# decoder.net
KiCad netlist of a schematic drawn in EAGLE
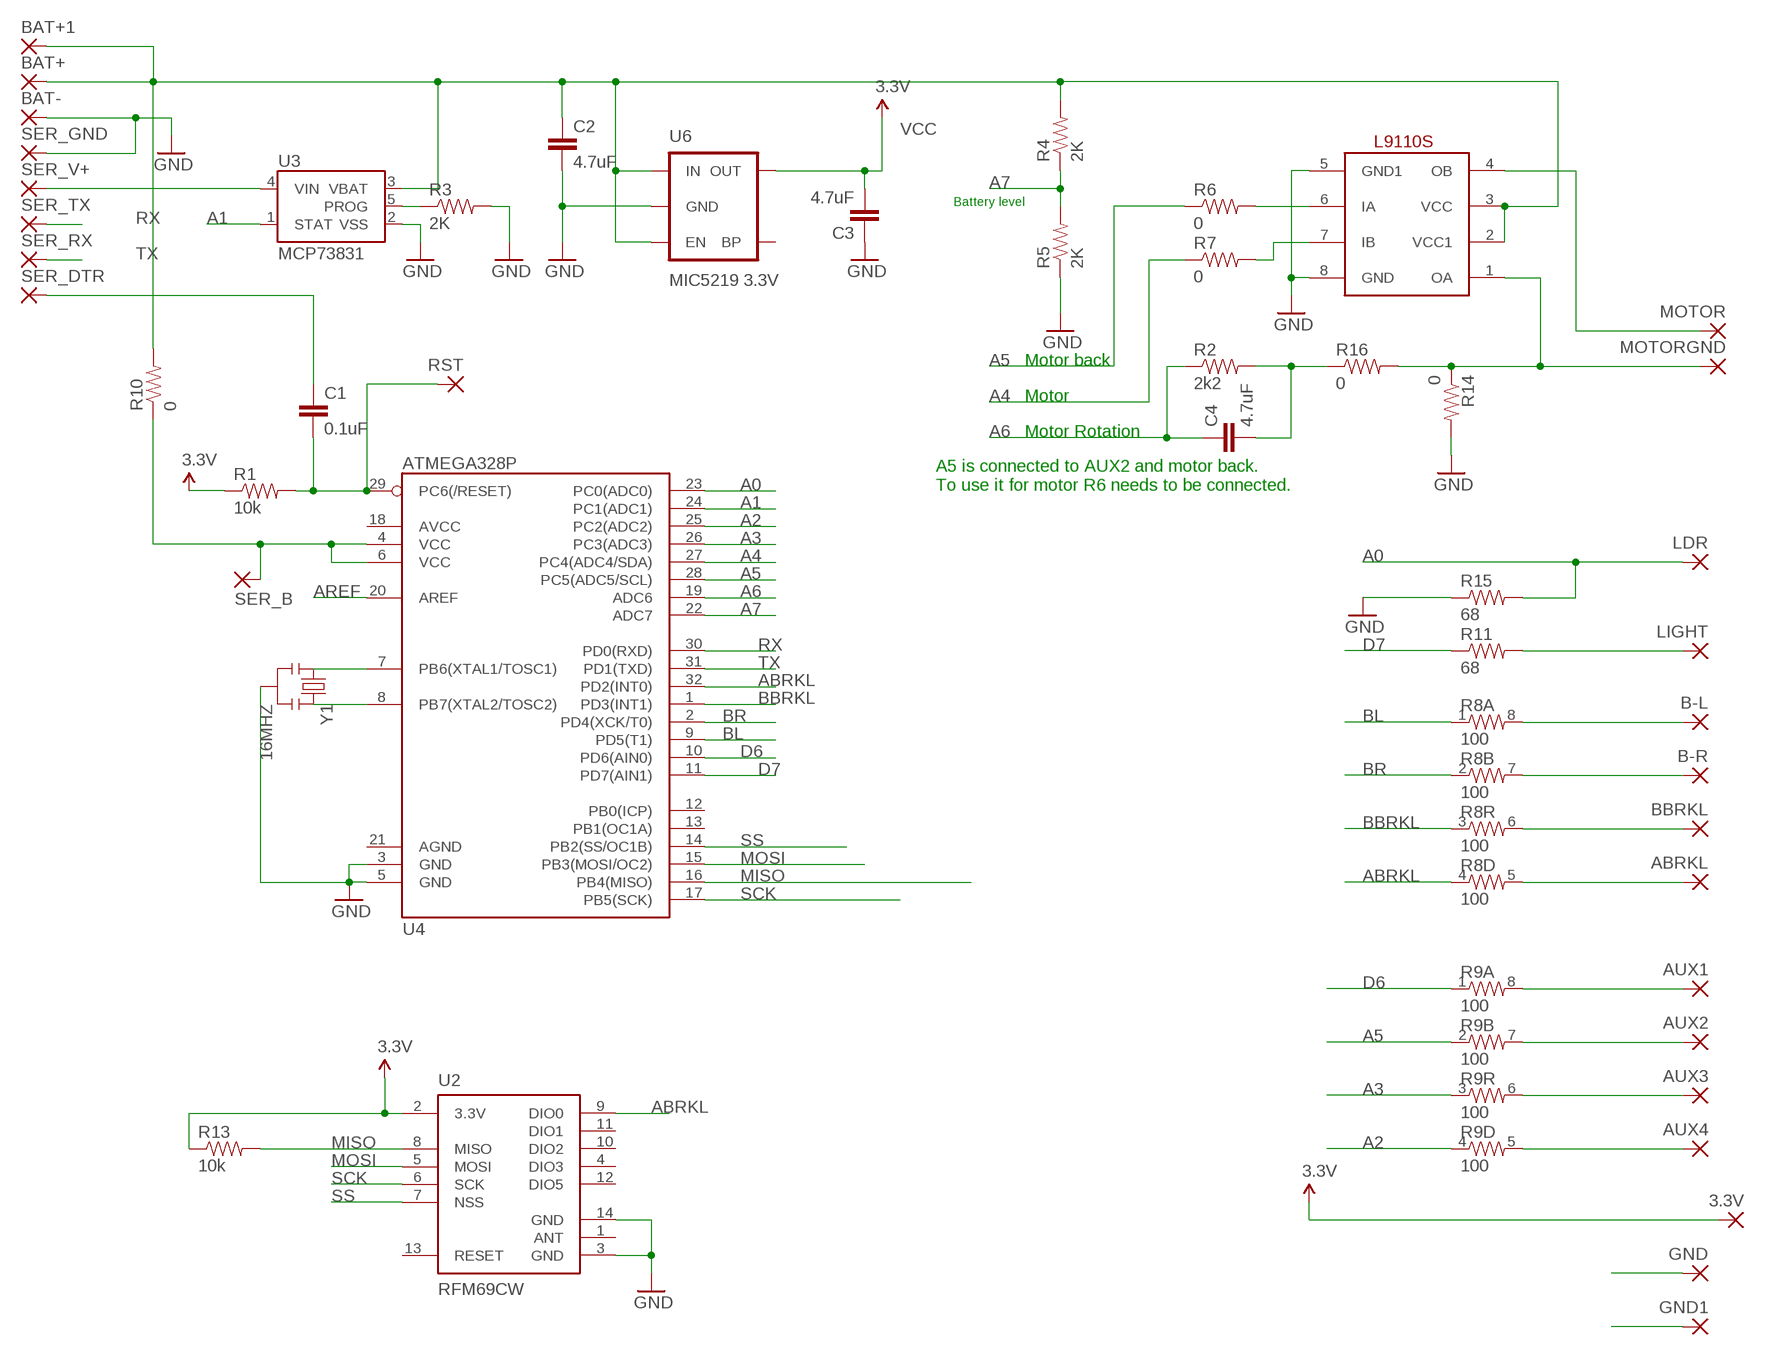
[diagram p0: schematic, sheet 1]

(export (version "E")
  (design (tool "Eeschema 10.0.6"))
  (components
    (comp (ref "3.3V")
      (value "SMD2")
      (footprint "eagle-import:SMD1,27-2,54")
      (libsource (lib "eagle-import") (part "SMD2"))
    )
    (comp (ref "ABRKL")
      (value "SMD2")
      (footprint "eagle-import:SMD1,27-2,54")
      (libsource (lib "eagle-import") (part "SMD2"))
    )
    (comp (ref "AUX1")
      (value "SMD2")
      (footprint "eagle-import:SMD1,27-2,54")
      (libsource (lib "eagle-import") (part "SMD2"))
    )
    (comp (ref "AUX2")
      (value "SMD2")
      (footprint "eagle-import:SMD1,27-2,54")
      (libsource (lib "eagle-import") (part "SMD2"))
    )
    (comp (ref "AUX3")
      (value "SMD2")
      (footprint "eagle-import:SMD1,27-2,54")
      (libsource (lib "eagle-import") (part "SMD2"))
    )
    (comp (ref "AUX4")
      (value "SMD2")
      (footprint "eagle-import:SMD1,27-2,54")
      (libsource (lib "eagle-import") (part "SMD2"))
    )
    (comp (ref "B-L")
      (value "SMD2")
      (footprint "eagle-import:SMD1,27-2,54")
      (libsource (lib "eagle-import") (part "SMD2"))
    )
    (comp (ref "B-R")
      (value "SMD2")
      (footprint "eagle-import:SMD1,27-2,54")
      (libsource (lib "eagle-import") (part "SMD2"))
    )
    (comp (ref "BAT+")
      (value "SMD2")
      (footprint "eagle-import:SMD1,27-2,54")
      (libsource (lib "eagle-import") (part "SMD2"))
    )
    (comp (ref "BAT+1")
      (value "SMD2")
      (footprint "eagle-import:SMD1,27-2,54")
      (libsource (lib "eagle-import") (part "SMD2"))
    )
    (comp (ref "BAT-")
      (value "SMD2")
      (footprint "eagle-import:SMD1,27-2,54")
      (libsource (lib "eagle-import") (part "SMD2"))
    )
    (comp (ref "BBRKL")
      (value "SMD2")
      (footprint "eagle-import:SMD1,27-2,54")
      (libsource (lib "eagle-import") (part "SMD2"))
    )
    (comp (ref "C1")
      (value "0.1uF")
      (footprint "eagle-import:0805")
      (libsource (lib "eagle-import") (part "CAP0805"))
    )
    (comp (ref "C2")
      (value "4.7uF")
      (footprint "eagle-import:0805")
      (libsource (lib "eagle-import") (part "CAP0805"))
    )
    (comp (ref "C3")
      (value "4.7uF")
      (footprint "eagle-import:0805")
      (libsource (lib "eagle-import") (part "CAP0805"))
    )
    (comp (ref "C4")
      (value "4.7uF")
      (footprint "eagle-import:0805")
      (libsource (lib "eagle-import") (part "CAP0805"))
    )
    (comp (ref "GND")
      (value "SMD2")
      (footprint "eagle-import:SMD1,27-2,54")
      (libsource (lib "eagle-import") (part "SMD2"))
    )
    (comp (ref "GND1")
      (value "SMD2")
      (footprint "eagle-import:SMD1,27-2,54")
      (libsource (lib "eagle-import") (part "SMD2"))
    )
    (comp (ref "LDR")
      (value "SMD2")
      (footprint "eagle-import:SMD1,27-2,54")
      (libsource (lib "eagle-import") (part "SMD2"))
    )
    (comp (ref "LIGHT")
      (value "SMD2")
      (footprint "eagle-import:SMD1,27-2,54")
      (libsource (lib "eagle-import") (part "SMD2"))
    )
    (comp (ref "MDRIVER")
      (value "L9110S")
      (footprint "eagle-import:SO08")
      (libsource (lib "eagle-import") (part "L9110S"))
    )
    (comp (ref "MOTOR")
      (value "SMD2")
      (footprint "eagle-import:SMD1,27-2,54")
      (libsource (lib "eagle-import") (part "SMD2"))
    )
    (comp (ref "MOTORGND")
      (value "SMD2")
      (footprint "eagle-import:SMD1,27-2,54")
      (libsource (lib "eagle-import") (part "SMD2"))
    )
    (comp (ref "R1")
      (value "10k")
      (footprint "eagle-import:0603-RES")
      (libsource (lib "eagle-import") (part "RESISTOR0603-RES"))
    )
    (comp (ref "R2")
      (value "2k2")
      (footprint "eagle-import:0603-RES")
      (libsource (lib "eagle-import") (part "RESISTOR0603-RES"))
    )
    (comp (ref "R3")
      (value "2K")
      (footprint "eagle-import:0603-RES")
      (libsource (lib "eagle-import") (part "RESISTOR0603-RES"))
    )
    (comp (ref "R4")
      (value "2K")
      (footprint "eagle-import:0603-RES")
      (libsource (lib "eagle-import") (part "RESISTOR0603-RES"))
    )
    (comp (ref "R5")
      (value "2K")
      (footprint "eagle-import:0603-RES")
      (libsource (lib "eagle-import") (part "RESISTOR0603-RES"))
    )
    (comp (ref "R6")
      (value "0")
      (footprint "eagle-import:0603-RES")
      (libsource (lib "eagle-import") (part "RESISTOR0603-RES"))
    )
    (comp (ref "R7")
      (value "0")
      (footprint "eagle-import:0603-RES")
      (libsource (lib "eagle-import") (part "RESISTOR0603-RES"))
    )
    (comp (ref "R8")
      (value "100")
      (footprint "eagle-import:0603-ARV")
      (libsource (lib "eagle-import") (part "RESISTOR-ARRAY0603-ARV"))
    )
    (comp (ref "R9")
      (value "100")
      (footprint "eagle-import:0603-ARV")
      (libsource (lib "eagle-import") (part "RESISTOR-ARRAY0603-ARV"))
    )
    (comp (ref "R10")
      (value "0")
      (footprint "eagle-import:0603-RES")
      (libsource (lib "eagle-import") (part "RESISTOR0603-RES"))
    )
    (comp (ref "R11")
      (value "68")
      (footprint "eagle-import:0603-RES")
      (libsource (lib "eagle-import") (part "RESISTOR0603-RES"))
    )
    (comp (ref "R13")
      (value "10k")
      (footprint "eagle-import:0603-RES")
      (libsource (lib "eagle-import") (part "RESISTOR0603-RES"))
    )
    (comp (ref "R14")
      (value "0")
      (footprint "eagle-import:0603-RES")
      (libsource (lib "eagle-import") (part "RESISTOR0603-RES"))
    )
    (comp (ref "R15")
      (value "68")
      (footprint "eagle-import:0603-RES")
      (libsource (lib "eagle-import") (part "RESISTOR0603-RES"))
    )
    (comp (ref "R16")
      (value "0")
      (footprint "eagle-import:0603-RES")
      (libsource (lib "eagle-import") (part "RESISTOR0603-RES"))
    )
    (comp (ref "RST")
      (value "SMD2")
      (footprint "eagle-import:SMD1,27-2,54")
      (libsource (lib "eagle-import") (part "SMD2"))
    )
    (comp (ref "SER_B")
      (value "SMD2")
      (footprint "eagle-import:SMD1,27-2,54")
      (libsource (lib "eagle-import") (part "SMD2"))
    )
    (comp (ref "SER_DTR")
      (value "SMD2")
      (footprint "eagle-import:SMD1,27-2,54")
      (libsource (lib "eagle-import") (part "SMD2"))
    )
    (comp (ref "SER_GND")
      (value "SMD2")
      (footprint "eagle-import:SMD1,27-2,54")
      (libsource (lib "eagle-import") (part "SMD2"))
    )
    (comp (ref "SER_RX")
      (value "SMD2")
      (footprint "eagle-import:SMD1,27-2,54")
      (libsource (lib "eagle-import") (part "SMD2"))
    )
    (comp (ref "SER_TX")
      (value "SMD2")
      (footprint "eagle-import:SMD1,27-2,54")
      (libsource (lib "eagle-import") (part "SMD2"))
    )
    (comp (ref "SER_V+")
      (value "SMD2")
      (footprint "eagle-import:SMD1,27-2,54")
      (libsource (lib "eagle-import") (part "SMD2"))
    )
    (comp (ref "U2")
      (value "RFM69CW")
      (footprint "eagle-import:RFM69CW-XXXS2")
      (libsource (lib "eagle-import") (part "RFM69CW"))
    )
    (comp (ref "U3")
      (value "MCP73831")
      (footprint "eagle-import:SOT23-5")
      (libsource (lib "eagle-import") (part "MCP73831"))
    )
    (comp (ref "U4")
      (value "ATMEGA328P")
      (footprint "eagle-import:TQFP32-08")
      (libsource (lib "eagle-import") (part "ATMEGA328_SMT"))
    )
    (comp (ref "U6")
      (value "MIC5219 3.3V")
      (footprint "eagle-import:SOT23-5")
      (libsource (lib "eagle-import") (part "V_REG_MIC52193.3V"))
    )
    (comp (ref "Y1")
      (value "16MHZ")
      (footprint "eagle-import:RESONATOR-SMD")
      (libsource (lib "eagle-import") (part "RESONATOR16MHZ"))
    )
  )
  (nets
    (net (code "1") (name "/A0") (class "Default")
      (node (ref "LDR") (pin "1") (pinfunction "P_1") (pintype "passive"))
      (node (ref "R15") (pin "2") (pinfunction "2_2") (pintype "passive"))
      (node (ref "U4") (pin "23") (pinfunction "PC0(ADC0)_23") (pintype "bidirectional"))
    )
    (net (code "2") (name "/A1") (class "Default")
      (node (ref "U3") (pin "1") (pinfunction "STAT_1") (pintype "output"))
      (node (ref "U4") (pin "24") (pinfunction "PC1(ADC1)_24") (pintype "bidirectional"))
    )
    (net (code "3") (name "/A2") (class "Default")
      (node (ref "R9") (pin "4") (pinfunction "1_4") (pintype "passive"))
      (node (ref "U4") (pin "25") (pinfunction "PC2(ADC2)_25") (pintype "bidirectional"))
    )
    (net (code "4") (name "/A3") (class "Default")
      (node (ref "R9") (pin "3") (pinfunction "1_3") (pintype "passive"))
      (node (ref "U4") (pin "26") (pinfunction "PC3(ADC3)_26") (pintype "bidirectional"))
    )
    (net (code "5") (name "/A4") (class "Default")
      (node (ref "R7") (pin "1") (pinfunction "1_1") (pintype "passive"))
      (node (ref "U4") (pin "27") (pinfunction "PC4(ADC4/SDA)_27") (pintype "bidirectional"))
    )
    (net (code "6") (name "/A5") (class "Default")
      (node (ref "R6") (pin "1") (pinfunction "1_1") (pintype "passive"))
      (node (ref "R9") (pin "2") (pinfunction "1_2") (pintype "passive"))
      (node (ref "U4") (pin "28") (pinfunction "PC5(ADC5/SCL)_28") (pintype "bidirectional"))
    )
    (net (code "7") (name "/A6") (class "Default")
      (node (ref "C4") (pin "1") (pinfunction "1_1") (pintype "passive"))
      (node (ref "R2") (pin "1") (pinfunction "1_1") (pintype "passive"))
      (node (ref "U4") (pin "19") (pinfunction "ADC6_19") (pintype "bidirectional"))
    )
    (net (code "8") (name "/A7") (class "Default")
      (node (ref "R4") (pin "1") (pinfunction "1_1") (pintype "passive"))
      (node (ref "R5") (pin "2") (pinfunction "2_2") (pintype "passive"))
      (node (ref "U4") (pin "22") (pinfunction "ADC7_22") (pintype "bidirectional"))
    )
    (net (code "9") (name "/ABRKL") (class "Default")
      (node (ref "R8") (pin "4") (pinfunction "1_4") (pintype "passive"))
      (node (ref "U2") (pin "9") (pinfunction "DIO0_9") (pintype "bidirectional"))
      (node (ref "U4") (pin "32") (pinfunction "PD2(INT0)_32") (pintype "bidirectional"))
    )
    (net (code "10") (name "/AREF") (class "Default")
      (node (ref "U4") (pin "20") (pinfunction "AREF_20") (pintype "bidirectional"))
    )
    (net (code "11") (name "/BBRKL") (class "Default")
      (node (ref "R8") (pin "3") (pinfunction "1_3") (pintype "passive"))
      (node (ref "U4") (pin "1") (pinfunction "PD3(INT1)_1") (pintype "bidirectional"))
    )
    (net (code "12") (name "/BL") (class "Default")
      (node (ref "R8") (pin "1") (pinfunction "1_1") (pintype "passive"))
      (node (ref "U4") (pin "9") (pinfunction "PD5(T1)_9") (pintype "bidirectional"))
    )
    (net (code "13") (name "/BR") (class "Default")
      (node (ref "R8") (pin "2") (pinfunction "1_2") (pintype "passive"))
      (node (ref "U4") (pin "2") (pinfunction "PD4(XCK/T0)_2") (pintype "bidirectional"))
    )
    (net (code "14") (name "/D6") (class "Default")
      (node (ref "R9") (pin "1") (pinfunction "1_1") (pintype "passive"))
      (node (ref "U4") (pin "10") (pinfunction "PD6(AIN0)_10") (pintype "bidirectional"))
    )
    (net (code "15") (name "/D7") (class "Default")
      (node (ref "R11") (pin "1") (pinfunction "1_1") (pintype "passive"))
      (node (ref "U4") (pin "11") (pinfunction "PD7(AIN1)_11") (pintype "bidirectional"))
    )
    (net (code "16") (name "/MISO") (class "Default")
      (node (ref "R13") (pin "2") (pinfunction "2_2") (pintype "passive"))
      (node (ref "U2") (pin "8") (pinfunction "MISO_8") (pintype "bidirectional"))
      (node (ref "U4") (pin "16") (pinfunction "PB4(MISO)_16") (pintype "bidirectional"))
    )
    (net (code "17") (name "/MOSI") (class "Default")
      (node (ref "U2") (pin "5") (pinfunction "MOSI_5") (pintype "input"))
      (node (ref "U4") (pin "15") (pinfunction "PB3(MOSI/OC2)_15") (pintype "bidirectional"))
    )
    (net (code "18") (name "/RX") (class "Default")
      (node (ref "SER_TX") (pin "1") (pinfunction "P_1") (pintype "passive"))
      (node (ref "U4") (pin "30") (pinfunction "PD0(RXD)_30") (pintype "bidirectional"))
    )
    (net (code "19") (name "/SCK") (class "Default")
      (node (ref "U2") (pin "6") (pinfunction "SCK_6") (pintype "input"))
      (node (ref "U4") (pin "17") (pinfunction "PB5(SCK)_17") (pintype "bidirectional"))
    )
    (net (code "20") (name "/SS") (class "Default")
      (node (ref "U2") (pin "7") (pinfunction "NSS_7") (pintype "input"))
      (node (ref "U4") (pin "14") (pinfunction "PB2(SS/OC1B)_14") (pintype "bidirectional"))
    )
    (net (code "21") (name "/TX") (class "Default")
      (node (ref "SER_RX") (pin "1") (pinfunction "P_1") (pintype "passive"))
      (node (ref "U4") (pin "31") (pinfunction "PD1(TXD)_31") (pintype "bidirectional"))
    )
    (net (code "22") (name "3.3V") (class "Default")
      (node (ref "3.3V") (pin "1") (pinfunction "P_1") (pintype "passive"))
      (node (ref "C3") (pin "2") (pinfunction "2_2") (pintype "passive"))
      (node (ref "R1") (pin "1") (pinfunction "1_1") (pintype "passive"))
      (node (ref "R13") (pin "1") (pinfunction "1_1") (pintype "passive"))
      (node (ref "U2") (pin "2") (pinfunction "3.3V_2") (pintype "power_in"))
      (node (ref "U6") (pin "5") (pinfunction "OUT_5") (pintype "passive"))
    )
    (net (code "23") (name "GND") (class "Default")
      (node (ref "BAT-") (pin "1") (pinfunction "P_1") (pintype "passive"))
      (node (ref "C2") (pin "2") (pinfunction "2_2") (pintype "passive"))
      (node (ref "C3") (pin "1") (pinfunction "1_1") (pintype "passive"))
      (node (ref "GND") (pin "1") (pinfunction "P_1") (pintype "passive"))
      (node (ref "GND1") (pin "1") (pinfunction "P_1") (pintype "passive"))
      (node (ref "MDRIVER") (pin "5") (pinfunction "GND1_5") (pintype "passive"))
      (node (ref "MDRIVER") (pin "8") (pinfunction "GND_8") (pintype "output"))
      (node (ref "R14") (pin "2") (pinfunction "2_2") (pintype "passive"))
      (node (ref "R15") (pin "1") (pinfunction "1_1") (pintype "passive"))
      (node (ref "R3") (pin "2") (pinfunction "2_2") (pintype "passive"))
      (node (ref "R5") (pin "1") (pinfunction "1_1") (pintype "passive"))
      (node (ref "SER_GND") (pin "1") (pinfunction "P_1") (pintype "passive"))
      (node (ref "U2") (pin "14") (pinfunction "GND_14") (pintype "power_in"))
      (node (ref "U2") (pin "3") (pinfunction "GND_3") (pintype "power_in"))
      (node (ref "U3") (pin "2") (pinfunction "VSS_2") (pintype "power_in"))
      (node (ref "U4") (pin "3") (pinfunction "GND_3") (pintype "bidirectional"))
      (node (ref "U4") (pin "5") (pinfunction "GND_5") (pintype "bidirectional"))
      (node (ref "U6") (pin "2") (pinfunction "GND_2") (pintype "input"))
      (node (ref "Y1") (pin "2") (pinfunction "2_2") (pintype "passive"))
    )
    (net (code "24") (name "Net-(ABRKL-P)") (class "Default")
      (node (ref "ABRKL") (pin "1") (pinfunction "P_1") (pintype "passive"))
      (node (ref "R8") (pin "5") (pinfunction "2_5") (pintype "passive"))
    )
    (net (code "25") (name "Net-(AUX1-P)") (class "Default")
      (node (ref "AUX1") (pin "1") (pinfunction "P_1") (pintype "passive"))
      (node (ref "R9") (pin "8") (pinfunction "2_8") (pintype "passive"))
    )
    (net (code "26") (name "Net-(AUX2-P)") (class "Default")
      (node (ref "AUX2") (pin "1") (pinfunction "P_1") (pintype "passive"))
      (node (ref "R9") (pin "7") (pinfunction "2_7") (pintype "passive"))
    )
    (net (code "27") (name "Net-(AUX3-P)") (class "Default")
      (node (ref "AUX3") (pin "1") (pinfunction "P_1") (pintype "passive"))
      (node (ref "R9") (pin "6") (pinfunction "2_6") (pintype "passive"))
    )
    (net (code "28") (name "Net-(AUX4-P)") (class "Default")
      (node (ref "AUX4") (pin "1") (pinfunction "P_1") (pintype "passive"))
      (node (ref "R9") (pin "5") (pinfunction "2_5") (pintype "passive"))
    )
    (net (code "29") (name "Net-(B-L-P)") (class "Default")
      (node (ref "B-L") (pin "1") (pinfunction "P_1") (pintype "passive"))
      (node (ref "R8") (pin "8") (pinfunction "2_8") (pintype "passive"))
    )
    (net (code "30") (name "Net-(B-R-P)") (class "Default")
      (node (ref "B-R") (pin "1") (pinfunction "P_1") (pintype "passive"))
      (node (ref "R8") (pin "7") (pinfunction "2_7") (pintype "passive"))
    )
    (net (code "31") (name "Net-(BAT+-P)") (class "Default")
      (node (ref "BAT+") (pin "1") (pinfunction "P_1") (pintype "passive"))
      (node (ref "BAT+1") (pin "1") (pinfunction "P_1") (pintype "passive"))
      (node (ref "C2") (pin "1") (pinfunction "1_1") (pintype "passive"))
      (node (ref "MDRIVER") (pin "2") (pinfunction "VCC1_2") (pintype "input"))
      (node (ref "MDRIVER") (pin "3") (pinfunction "VCC_3") (pintype "input"))
      (node (ref "R10") (pin "2") (pinfunction "2_2") (pintype "passive"))
      (node (ref "R4") (pin "2") (pinfunction "2_2") (pintype "passive"))
      (node (ref "U3") (pin "3") (pinfunction "VBAT_3") (pintype "power_in"))
      (node (ref "U6") (pin "1") (pinfunction "IN_1") (pintype "input"))
      (node (ref "U6") (pin "3") (pinfunction "EN_3") (pintype "input"))
    )
    (net (code "32") (name "Net-(BBRKL-P)") (class "Default")
      (node (ref "BBRKL") (pin "1") (pinfunction "P_1") (pintype "passive"))
      (node (ref "R8") (pin "6") (pinfunction "2_6") (pintype "passive"))
    )
    (net (code "33") (name "Net-(C4-Pad2)") (class "Default")
      (node (ref "C4") (pin "2") (pinfunction "2_2") (pintype "passive"))
      (node (ref "R16") (pin "1") (pinfunction "1_1") (pintype "passive"))
      (node (ref "R2") (pin "2") (pinfunction "2_2") (pintype "passive"))
    )
    (net (code "34") (name "Net-(LIGHT-P)") (class "Default")
      (node (ref "LIGHT") (pin "1") (pinfunction "P_1") (pintype "passive"))
      (node (ref "R11") (pin "2") (pinfunction "2_2") (pintype "passive"))
    )
    (net (code "35") (name "Net-(MDRIVER-IA)") (class "Default")
      (node (ref "MDRIVER") (pin "6") (pinfunction "IA_6") (pintype "passive"))
      (node (ref "R6") (pin "2") (pinfunction "2_2") (pintype "passive"))
    )
    (net (code "36") (name "Net-(MDRIVER-IB)") (class "Default")
      (node (ref "MDRIVER") (pin "7") (pinfunction "IB_7") (pintype "output"))
      (node (ref "R7") (pin "2") (pinfunction "2_2") (pintype "passive"))
    )
    (net (code "37") (name "Net-(MDRIVER-OA)") (class "Default")
      (node (ref "MDRIVER") (pin "1") (pinfunction "OA_1") (pintype "power_in"))
      (node (ref "MOTORGND") (pin "1") (pinfunction "P_1") (pintype "passive"))
      (node (ref "R14") (pin "1") (pinfunction "1_1") (pintype "passive"))
      (node (ref "R16") (pin "2") (pinfunction "2_2") (pintype "passive"))
    )
    (net (code "38") (name "Net-(MDRIVER-OB)") (class "Default")
      (node (ref "MDRIVER") (pin "4") (pinfunction "OB_4") (pintype "power_in"))
      (node (ref "MOTOR") (pin "1") (pinfunction "P_1") (pintype "passive"))
    )
    (net (code "39") (name "Net-(RST-P)") (class "Default")
      (node (ref "C1") (pin "2") (pinfunction "2_2") (pintype "passive"))
      (node (ref "R1") (pin "2") (pinfunction "2_2") (pintype "passive"))
      (node (ref "RST") (pin "1") (pinfunction "P_1") (pintype "passive"))
      (node (ref "U4") (pin "29") (pinfunction "PC6(/RESET)_29") (pintype "bidirectional"))
    )
    (net (code "40") (name "Net-(SER_B-P)") (class "Default")
      (node (ref "R10") (pin "1") (pinfunction "1_1") (pintype "passive"))
      (node (ref "SER_B") (pin "1") (pinfunction "P_1") (pintype "passive"))
      (node (ref "U4") (pin "4") (pinfunction "VCC_4") (pintype "bidirectional"))
      (node (ref "U4") (pin "6") (pinfunction "VCC_6") (pintype "bidirectional"))
    )
    (net (code "41") (name "Net-(SER_DTR-P)") (class "Default")
      (node (ref "C1") (pin "1") (pinfunction "1_1") (pintype "passive"))
      (node (ref "SER_DTR") (pin "1") (pinfunction "P_1") (pintype "passive"))
    )
    (net (code "42") (name "Net-(SER_V+-P)") (class "Default")
      (node (ref "SER_V+") (pin "1") (pinfunction "P_1") (pintype "passive"))
      (node (ref "U3") (pin "4") (pinfunction "VIN_4") (pintype "power_in"))
    )
    (net (code "43") (name "Net-(U3-PROG)") (class "Default")
      (node (ref "R3") (pin "1") (pinfunction "1_1") (pintype "passive"))
      (node (ref "U3") (pin "5") (pinfunction "PROG_5") (pintype "input"))
    )
    (net (code "44") (name "Net-(U4-PB6(XTAL1{slash}TOSC1))") (class "Default")
      (node (ref "U4") (pin "7") (pinfunction "PB6(XTAL1/TOSC1)_7") (pintype "bidirectional"))
      (node (ref "Y1") (pin "1") (pinfunction "1_1") (pintype "passive"))
    )
    (net (code "45") (name "Net-(U4-PB7(XTAL2{slash}TOSC2))") (class "Default")
      (node (ref "U4") (pin "8") (pinfunction "PB7(XTAL2/TOSC2)_8") (pintype "bidirectional"))
      (node (ref "Y1") (pin "3") (pinfunction "3_3") (pintype "passive"))
    )
    (net (code "46") (name "unconnected-(U2-ANT-Pad1)") (class "Default")
      (node (ref "U2") (pin "1") (pinfunction "ANT_1") (pintype "passive"))
    )
    (net (code "47") (name "unconnected-(U2-DIO1-Pad11)") (class "Default")
      (node (ref "U2") (pin "11") (pinfunction "DIO1_11") (pintype "bidirectional"))
    )
    (net (code "48") (name "unconnected-(U2-DIO2-Pad10)") (class "Default")
      (node (ref "U2") (pin "10") (pinfunction "DIO2_10") (pintype "bidirectional"))
    )
    (net (code "49") (name "unconnected-(U2-DIO3-Pad4)") (class "Default")
      (node (ref "U2") (pin "4") (pinfunction "DIO3_4") (pintype "bidirectional"))
    )
    (net (code "50") (name "unconnected-(U2-DIO5-Pad12)") (class "Default")
      (node (ref "U2") (pin "12") (pinfunction "DIO5_12") (pintype "bidirectional"))
    )
    (net (code "51") (name "unconnected-(U2-RESET-Pad13)") (class "Default")
      (node (ref "U2") (pin "13") (pinfunction "RESET_13") (pintype "input"))
    )
    (net (code "52") (name "unconnected-(U4-AGND-Pad21)") (class "Default")
      (node (ref "U4") (pin "21") (pinfunction "AGND_21") (pintype "bidirectional"))
    )
    (net (code "53") (name "unconnected-(U4-AVCC-Pad18)") (class "Default")
      (node (ref "U4") (pin "18") (pinfunction "AVCC_18") (pintype "bidirectional"))
    )
    (net (code "54") (name "unconnected-(U4-PB0(ICP)-Pad12)") (class "Default")
      (node (ref "U4") (pin "12") (pinfunction "PB0(ICP)_12") (pintype "bidirectional"))
    )
    (net (code "55") (name "unconnected-(U4-PB1(OC1A)-Pad13)") (class "Default")
      (node (ref "U4") (pin "13") (pinfunction "PB1(OC1A)_13") (pintype "bidirectional"))
    )
    (net (code "56") (name "unconnected-(U6-BP-Pad4)") (class "Default")
      (node (ref "U6") (pin "4") (pinfunction "BP_4") (pintype "input"))
    )
  )
)
